# Resolver_to_digital_concerter_AD2S1210.net
KiCad netlist of a schematic drawn in EAGLE
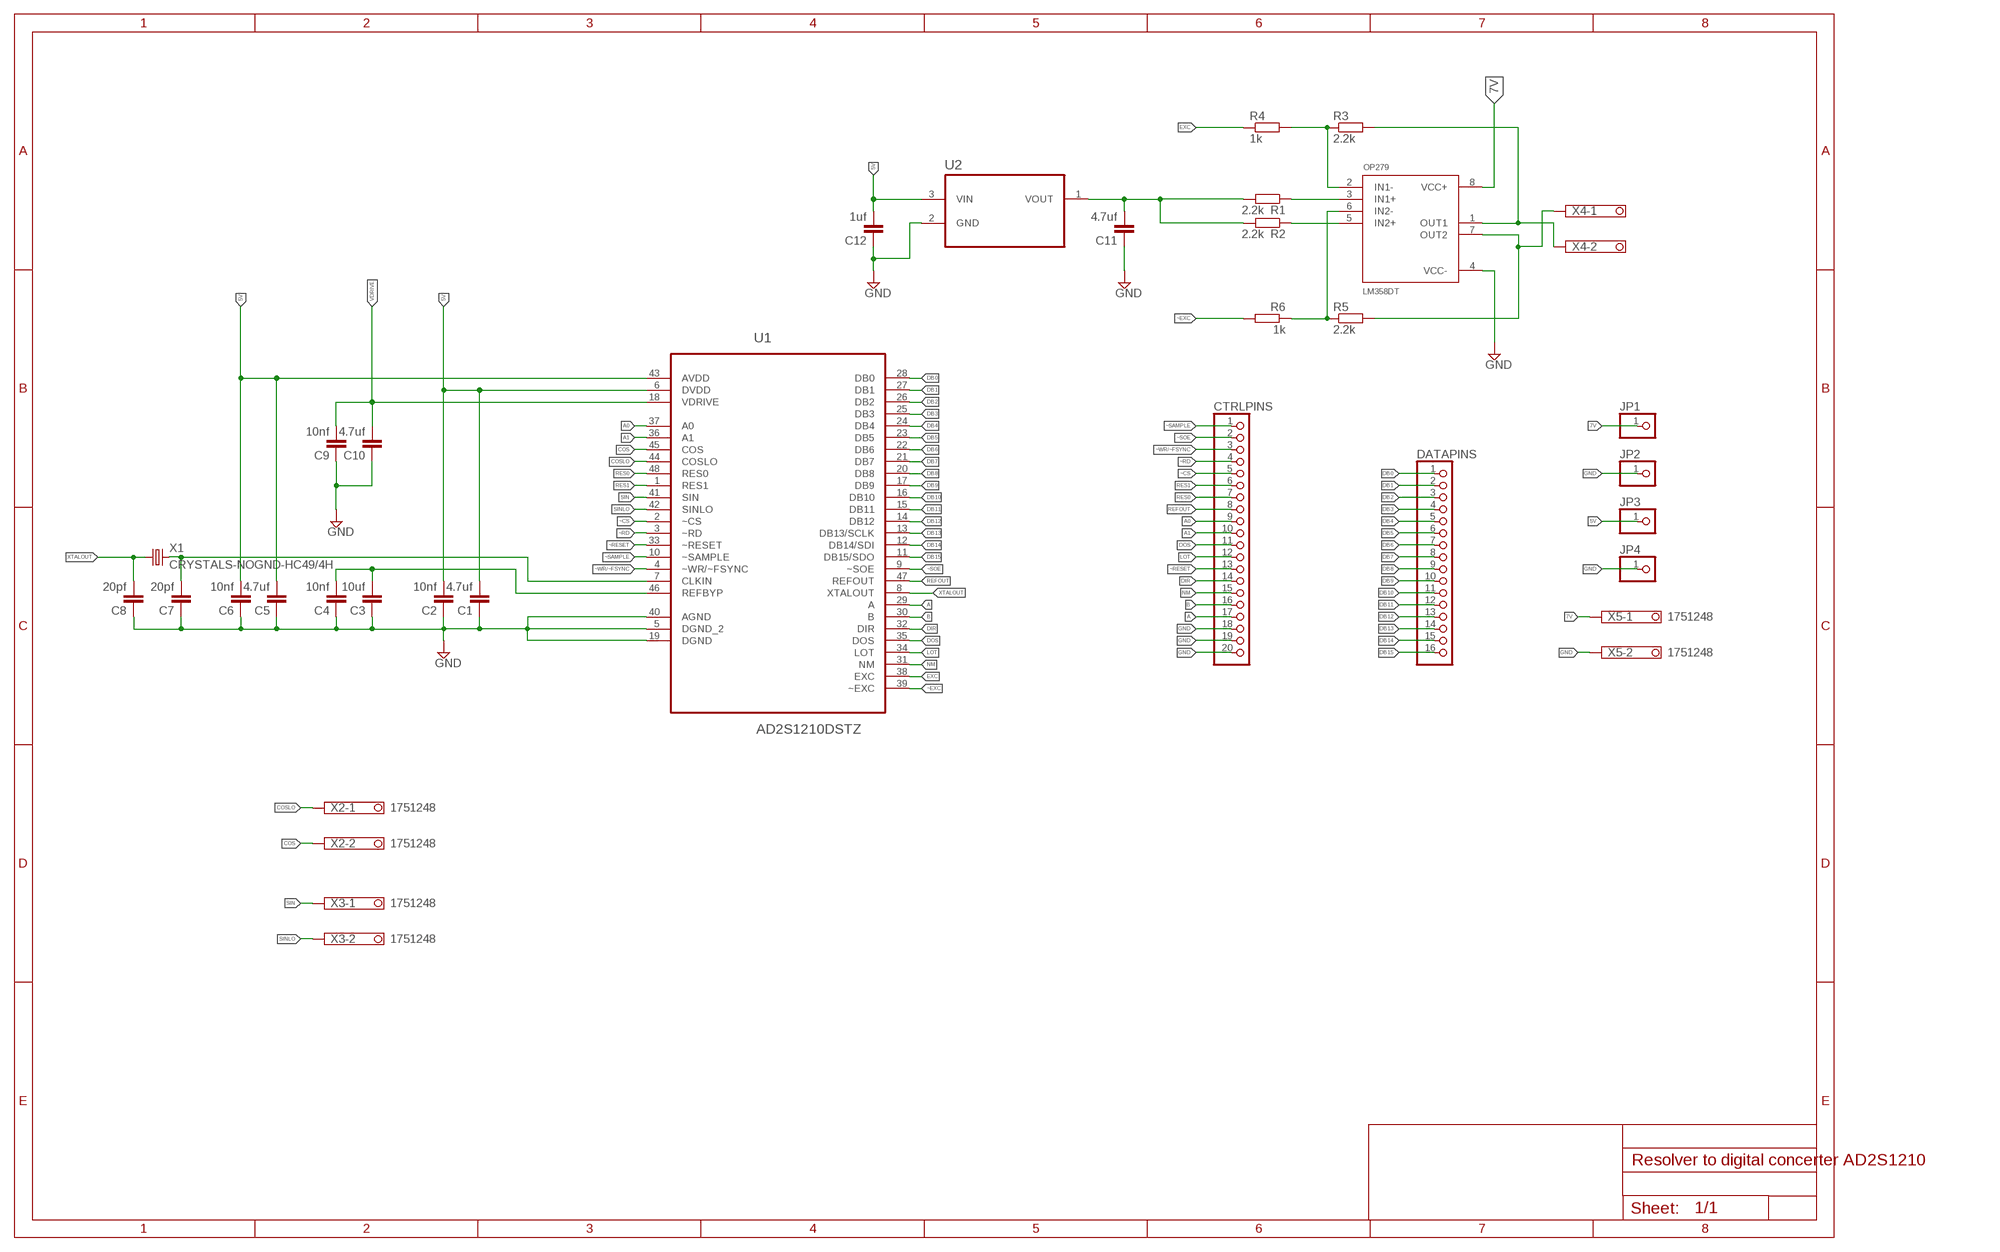
[diagram p0: schematic, sheet 1]

(export (version "E")
  (design (tool "Eeschema 10.0.6"))
  (components
    (comp (ref "C1")
      (value "4.7uf")
      (footprint "eagle-import:C0805")
      (libsource (lib "eagle-import") (part "C-EUC0805"))
    )
    (comp (ref "C2")
      (value "10nf")
      (footprint "eagle-import:C0805")
      (libsource (lib "eagle-import") (part "C-EUC0805"))
    )
    (comp (ref "C3")
      (value "10uf")
      (footprint "eagle-import:C0805")
      (libsource (lib "eagle-import") (part "C-EUC0805"))
    )
    (comp (ref "C4")
      (value "10nf")
      (footprint "eagle-import:C0805")
      (libsource (lib "eagle-import") (part "C-EUC0805"))
    )
    (comp (ref "C5")
      (value "4.7uf")
      (footprint "eagle-import:C0805")
      (libsource (lib "eagle-import") (part "C-EUC0805"))
    )
    (comp (ref "C6")
      (value "10nf")
      (footprint "eagle-import:C0805")
      (libsource (lib "eagle-import") (part "C-EUC0805"))
    )
    (comp (ref "C7")
      (value "20pf")
      (footprint "eagle-import:C0805")
      (libsource (lib "eagle-import") (part "C-EUC0805"))
    )
    (comp (ref "C8")
      (value "20pf")
      (footprint "eagle-import:C0805")
      (libsource (lib "eagle-import") (part "C-EUC0805"))
    )
    (comp (ref "C9")
      (value "10nf")
      (footprint "eagle-import:C0805")
      (libsource (lib "eagle-import") (part "C-EUC0805"))
    )
    (comp (ref "C10")
      (value "4.7uf")
      (footprint "eagle-import:C0805")
      (libsource (lib "eagle-import") (part "C-EUC0805"))
    )
    (comp (ref "C11")
      (value "4.7uf")
      (footprint "eagle-import:C0805")
      (libsource (lib "eagle-import") (part "C-EUC0805"))
    )
    (comp (ref "C12")
      (value "1uf")
      (footprint "eagle-import:C0805")
      (libsource (lib "eagle-import") (part "C-EUC0805"))
    )
    (comp (ref "CTRLPINS")
      (value "PINHD-1X20")
      (footprint "eagle-import:1X20")
      (libsource (lib "eagle-import") (part "PINHD-1X20"))
    )
    (comp (ref "DATAPINS")
      (value "PINHD-1X16")
      (footprint "eagle-import:1X16")
      (libsource (lib "eagle-import") (part "PINHD-1X16"))
    )
    (comp (ref "JP1")
      (value "PINHD-1X1")
      (footprint "eagle-import:1X01")
      (libsource (lib "eagle-import") (part "PINHD-1X1"))
    )
    (comp (ref "JP2")
      (value "PINHD-1X1")
      (footprint "eagle-import:1X01")
      (libsource (lib "eagle-import") (part "PINHD-1X1"))
    )
    (comp (ref "JP3")
      (value "PINHD-1X1")
      (footprint "eagle-import:1X01")
      (libsource (lib "eagle-import") (part "PINHD-1X1"))
    )
    (comp (ref "JP4")
      (value "PINHD-1X1")
      (footprint "eagle-import:1X01")
      (libsource (lib "eagle-import") (part "PINHD-1X1"))
    )
    (comp (ref "OP279")
      (value "LM358DT")
      (footprint "eagle-import:SOIC127P600X175-8N")
      (fields (field (name "MF") "STMicroelectronics"))
      (libsource (lib "eagle-import") (part "LM358DT"))
    )
    (comp (ref "R1")
      (value "2.2k")
      (footprint "eagle-import:R0805")
      (libsource (lib "eagle-import") (part "R-EU_R0805"))
    )
    (comp (ref "R2")
      (value "2.2k")
      (footprint "eagle-import:R0805")
      (libsource (lib "eagle-import") (part "R-EU_R0805"))
    )
    (comp (ref "R3")
      (value "2.2k")
      (footprint "eagle-import:R0805")
      (libsource (lib "eagle-import") (part "R-EU_R0805"))
    )
    (comp (ref "R4")
      (value "1k")
      (footprint "eagle-import:R0805")
      (libsource (lib "eagle-import") (part "R-EU_R0805"))
    )
    (comp (ref "R5")
      (value "2.2k")
      (footprint "eagle-import:R0805")
      (libsource (lib "eagle-import") (part "R-EU_R0805"))
    )
    (comp (ref "R6")
      (value "1k")
      (footprint "eagle-import:R0805")
      (libsource (lib "eagle-import") (part "R-EU_R0805"))
    )
    (comp (ref "U1")
      (value "AD2S1210DSTZ")
      (footprint "eagle-import:QFP50P900X900X160-48N")
      (fields (field (name "MF") "Analog Devices"))
      (libsource (lib "eagle-import") (part "AD2S1210DSTZ"))
    )
    (comp (ref "U2")
      (value "AD1582BRTZ-REEL7")
      (footprint "eagle-import:SOT95P237X112-3N")
      (fields (field (name "MF") "Analog Devices"))
      (libsource (lib "eagle-import") (part "AD1582BRTZ-REEL7"))
    )
    (comp (ref "X1")
      (value "CRYSTALS-NOGND-HC49/4H")
      (footprint "eagle-import:HC49")
      (libsource (lib "eagle-import") (part "CRYSTALS-NOGND-HC49/4H"))
    )
    (comp (ref "X2")
      (value "1751248")
      (footprint "eagle-import:1751248")
      (libsource (lib "eagle-import") (part "1751248"))
    )
    (comp (ref "X3")
      (value "1751248")
      (footprint "eagle-import:1751248")
      (libsource (lib "eagle-import") (part "1751248"))
    )
    (comp (ref "X4")
      (value "1751248")
      (footprint "eagle-import:1751248")
      (libsource (lib "eagle-import") (part "1751248"))
    )
    (comp (ref "X5")
      (value "1751248")
      (footprint "eagle-import:1751248")
      (libsource (lib "eagle-import") (part "1751248"))
    )
  )
  (nets
    (net (code "1") (name "/~{CS}") (class "Default")
      (node (ref "CTRLPINS") (pin "5") (pinfunction "5_5") (pintype "passive"))
      (node (ref "U1") (pin "2") (pinfunction "~{CS}_2") (pintype "input"))
    )
    (net (code "2") (name "/~{EXC}") (class "Default")
      (node (ref "R6") (pin "2") (pinfunction "2_2") (pintype "passive"))
      (node (ref "U1") (pin "39") (pinfunction "~{EXC}_39") (pintype "output"))
    )
    (net (code "3") (name "/~{RD}") (class "Default")
      (node (ref "CTRLPINS") (pin "4") (pinfunction "4_4") (pintype "passive"))
      (node (ref "U1") (pin "3") (pinfunction "~{RD}_3") (pintype "input"))
    )
    (net (code "4") (name "/~{RESET}") (class "Default")
      (node (ref "CTRLPINS") (pin "13") (pinfunction "13_13") (pintype "passive"))
      (node (ref "U1") (pin "33") (pinfunction "~{RESET}_33") (pintype "input"))
    )
    (net (code "5") (name "/~{SAMPLE}") (class "Default")
      (node (ref "CTRLPINS") (pin "1") (pinfunction "1_1") (pintype "passive"))
      (node (ref "U1") (pin "10") (pinfunction "~{SAMPLE}_10") (pintype "input"))
    )
    (net (code "6") (name "/~{SOE}") (class "Default")
      (node (ref "CTRLPINS") (pin "2") (pinfunction "2_2") (pintype "passive"))
      (node (ref "U1") (pin "9") (pinfunction "~{SOE}_9") (pintype "input"))
    )
    (net (code "7") (name "/~{WR{slash}}FSYNC") (class "Default")
      (node (ref "CTRLPINS") (pin "3") (pinfunction "3_3") (pintype "passive"))
      (node (ref "U1") (pin "4") (pinfunction "~{WR/}FSYNC_4") (pintype "input"))
    )
    (net (code "8") (name "5V") (class "Default")
      (node (ref "C1") (pin "2") (pinfunction "2_2") (pintype "passive"))
      (node (ref "C12") (pin "2") (pinfunction "2_2") (pintype "passive"))
      (node (ref "C2") (pin "2") (pinfunction "2_2") (pintype "passive"))
      (node (ref "C5") (pin "2") (pinfunction "2_2") (pintype "passive"))
      (node (ref "C6") (pin "2") (pinfunction "2_2") (pintype "passive"))
      (node (ref "JP3") (pin "1") (pinfunction "1_1") (pintype "passive"))
      (node (ref "U1") (pin "43") (pinfunction "AVDD_43") (pintype "power_in"))
      (node (ref "U1") (pin "6") (pinfunction "DVDD_6") (pintype "power_in"))
      (node (ref "U2") (pin "3") (pinfunction "VIN_3") (pintype "input"))
    )
    (net (code "9") (name "7V") (class "Default")
      (node (ref "JP1") (pin "1") (pinfunction "1_1") (pintype "passive"))
      (node (ref "OP279") (pin "8") (pinfunction "VCC+_8") (pintype "power_in"))
      (node (ref "X5") (pin "1") (pinfunction "K_1") (pintype "passive"))
    )
    (net (code "10") (name "A") (class "Default")
      (node (ref "CTRLPINS") (pin "17") (pinfunction "17_17") (pintype "passive"))
      (node (ref "U1") (pin "29") (pinfunction "A_29") (pintype "output"))
    )
    (net (code "11") (name "A0") (class "Default")
      (node (ref "CTRLPINS") (pin "9") (pinfunction "9_9") (pintype "passive"))
      (node (ref "U1") (pin "37") (pinfunction "A0_37") (pintype "input"))
    )
    (net (code "12") (name "A1") (class "Default")
      (node (ref "CTRLPINS") (pin "10") (pinfunction "10_10") (pintype "passive"))
      (node (ref "U1") (pin "36") (pinfunction "A1_36") (pintype "input"))
    )
    (net (code "13") (name "B") (class "Default")
      (node (ref "CTRLPINS") (pin "16") (pinfunction "16_16") (pintype "passive"))
      (node (ref "U1") (pin "30") (pinfunction "B_30") (pintype "output"))
    )
    (net (code "14") (name "COS") (class "Default")
      (node (ref "U1") (pin "45") (pinfunction "COS_45") (pintype "input"))
      (node (ref "X2") (pin "2") (pinfunction "K_2") (pintype "passive"))
    )
    (net (code "15") (name "COSLO") (class "Default")
      (node (ref "U1") (pin "44") (pinfunction "COSLO_44") (pintype "input"))
      (node (ref "X2") (pin "1") (pinfunction "K_1") (pintype "passive"))
    )
    (net (code "16") (name "DB0") (class "Default")
      (node (ref "DATAPINS") (pin "1") (pinfunction "1_1") (pintype "passive"))
      (node (ref "U1") (pin "28") (pinfunction "DB0_28") (pintype "output"))
    )
    (net (code "17") (name "DB1") (class "Default")
      (node (ref "DATAPINS") (pin "2") (pinfunction "2_2") (pintype "passive"))
      (node (ref "U1") (pin "27") (pinfunction "DB1_27") (pintype "output"))
    )
    (net (code "18") (name "DB2") (class "Default")
      (node (ref "DATAPINS") (pin "3") (pinfunction "3_3") (pintype "passive"))
      (node (ref "U1") (pin "26") (pinfunction "DB2_26") (pintype "output"))
    )
    (net (code "19") (name "DB3") (class "Default")
      (node (ref "DATAPINS") (pin "4") (pinfunction "4_4") (pintype "passive"))
      (node (ref "U1") (pin "25") (pinfunction "DB3_25") (pintype "output"))
    )
    (net (code "20") (name "DB4") (class "Default")
      (node (ref "DATAPINS") (pin "5") (pinfunction "5_5") (pintype "passive"))
      (node (ref "U1") (pin "24") (pinfunction "DB4_24") (pintype "output"))
    )
    (net (code "21") (name "DB5") (class "Default")
      (node (ref "DATAPINS") (pin "6") (pinfunction "6_6") (pintype "passive"))
      (node (ref "U1") (pin "23") (pinfunction "DB5_23") (pintype "output"))
    )
    (net (code "22") (name "DB6") (class "Default")
      (node (ref "DATAPINS") (pin "7") (pinfunction "7_7") (pintype "passive"))
      (node (ref "U1") (pin "22") (pinfunction "DB6_22") (pintype "output"))
    )
    (net (code "23") (name "DB7") (class "Default")
      (node (ref "DATAPINS") (pin "8") (pinfunction "8_8") (pintype "passive"))
      (node (ref "U1") (pin "21") (pinfunction "DB7_21") (pintype "output"))
    )
    (net (code "24") (name "DB8") (class "Default")
      (node (ref "DATAPINS") (pin "9") (pinfunction "9_9") (pintype "passive"))
      (node (ref "U1") (pin "20") (pinfunction "DB8_20") (pintype "output"))
    )
    (net (code "25") (name "DB9") (class "Default")
      (node (ref "DATAPINS") (pin "10") (pinfunction "10_10") (pintype "passive"))
      (node (ref "U1") (pin "17") (pinfunction "DB9_17") (pintype "output"))
    )
    (net (code "26") (name "DB10") (class "Default")
      (node (ref "DATAPINS") (pin "11") (pinfunction "11_11") (pintype "passive"))
      (node (ref "U1") (pin "16") (pinfunction "DB10_16") (pintype "output"))
    )
    (net (code "27") (name "DB11") (class "Default")
      (node (ref "DATAPINS") (pin "12") (pinfunction "12_12") (pintype "passive"))
      (node (ref "U1") (pin "15") (pinfunction "DB11_15") (pintype "output"))
    )
    (net (code "28") (name "DB12") (class "Default")
      (node (ref "DATAPINS") (pin "13") (pinfunction "13_13") (pintype "passive"))
      (node (ref "U1") (pin "14") (pinfunction "DB12_14") (pintype "output"))
    )
    (net (code "29") (name "DB13") (class "Default")
      (node (ref "DATAPINS") (pin "14") (pinfunction "14_14") (pintype "passive"))
      (node (ref "U1") (pin "13") (pinfunction "DB13/SCLK_13") (pintype "bidirectional"))
    )
    (net (code "30") (name "DB14") (class "Default")
      (node (ref "DATAPINS") (pin "15") (pinfunction "15_15") (pintype "passive"))
      (node (ref "U1") (pin "12") (pinfunction "DB14/SDI_12") (pintype "bidirectional"))
    )
    (net (code "31") (name "DB15") (class "Default")
      (node (ref "DATAPINS") (pin "16") (pinfunction "16_16") (pintype "passive"))
      (node (ref "U1") (pin "11") (pinfunction "DB15/SDO_11") (pintype "output"))
    )
    (net (code "32") (name "DIR") (class "Default")
      (node (ref "CTRLPINS") (pin "14") (pinfunction "14_14") (pintype "passive"))
      (node (ref "U1") (pin "32") (pinfunction "DIR_32") (pintype "output"))
    )
    (net (code "33") (name "DOS") (class "Default")
      (node (ref "CTRLPINS") (pin "11") (pinfunction "11_11") (pintype "passive"))
      (node (ref "U1") (pin "35") (pinfunction "DOS_35") (pintype "output"))
    )
    (net (code "34") (name "EXC") (class "Default")
      (node (ref "R4") (pin "1") (pinfunction "1_1") (pintype "passive"))
      (node (ref "U1") (pin "38") (pinfunction "EXC_38") (pintype "output"))
    )
    (net (code "35") (name "GND") (class "Default")
      (node (ref "C1") (pin "1") (pinfunction "1_1") (pintype "passive"))
      (node (ref "C10") (pin "1") (pinfunction "1_1") (pintype "passive"))
      (node (ref "C11") (pin "1") (pinfunction "1_1") (pintype "passive"))
      (node (ref "C12") (pin "1") (pinfunction "1_1") (pintype "passive"))
      (node (ref "C2") (pin "1") (pinfunction "1_1") (pintype "passive"))
      (node (ref "C3") (pin "1") (pinfunction "1_1") (pintype "passive"))
      (node (ref "C4") (pin "1") (pinfunction "1_1") (pintype "passive"))
      (node (ref "C5") (pin "1") (pinfunction "1_1") (pintype "passive"))
      (node (ref "C6") (pin "1") (pinfunction "1_1") (pintype "passive"))
      (node (ref "C7") (pin "1") (pinfunction "1_1") (pintype "passive"))
      (node (ref "C8") (pin "1") (pinfunction "1_1") (pintype "passive"))
      (node (ref "C9") (pin "1") (pinfunction "1_1") (pintype "passive"))
      (node (ref "CTRLPINS") (pin "18") (pinfunction "18_18") (pintype "passive"))
      (node (ref "CTRLPINS") (pin "19") (pinfunction "19_19") (pintype "passive"))
      (node (ref "CTRLPINS") (pin "20") (pinfunction "20_20") (pintype "passive"))
      (node (ref "JP2") (pin "1") (pinfunction "1_1") (pintype "passive"))
      (node (ref "JP4") (pin "1") (pinfunction "1_1") (pintype "passive"))
      (node (ref "OP279") (pin "4") (pinfunction "VCC-_4") (pintype "power_in"))
      (node (ref "U1") (pin "19") (pinfunction "DGND_19") (pintype "passive"))
      (node (ref "U1") (pin "40") (pinfunction "AGND_40") (pintype "passive"))
      (node (ref "U1") (pin "5") (pinfunction "DGND_2_5") (pintype "passive"))
      (node (ref "U2") (pin "2") (pinfunction "GND_2") (pintype "passive"))
      (node (ref "X5") (pin "2") (pinfunction "K_2") (pintype "passive"))
    )
    (net (code "36") (name "LOT") (class "Default")
      (node (ref "CTRLPINS") (pin "12") (pinfunction "12_12") (pintype "passive"))
      (node (ref "U1") (pin "34") (pinfunction "LOT_34") (pintype "output"))
    )
    (net (code "37") (name "NM") (class "Default")
      (node (ref "CTRLPINS") (pin "15") (pinfunction "15_15") (pintype "passive"))
      (node (ref "U1") (pin "31") (pinfunction "NM_31") (pintype "output"))
    )
    (net (code "38") (name "Net-(OP279-IN1+)") (class "Default")
      (node (ref "OP279") (pin "3") (pinfunction "IN1+_3") (pintype "input"))
      (node (ref "R1") (pin "1") (pinfunction "1_1") (pintype "passive"))
    )
    (net (code "39") (name "Net-(OP279-IN1-)") (class "Default")
      (node (ref "OP279") (pin "2") (pinfunction "IN1-_2") (pintype "input"))
      (node (ref "R3") (pin "1") (pinfunction "1_1") (pintype "passive"))
      (node (ref "R4") (pin "2") (pinfunction "2_2") (pintype "passive"))
    )
    (net (code "40") (name "Net-(OP279-IN2+)") (class "Default")
      (node (ref "OP279") (pin "5") (pinfunction "IN2+_5") (pintype "input"))
      (node (ref "R2") (pin "1") (pinfunction "1_1") (pintype "passive"))
    )
    (net (code "41") (name "Net-(OP279-IN2-)") (class "Default")
      (node (ref "OP279") (pin "6") (pinfunction "IN2-_6") (pintype "input"))
      (node (ref "R5") (pin "1") (pinfunction "1_1") (pintype "passive"))
      (node (ref "R6") (pin "1") (pinfunction "1_1") (pintype "passive"))
    )
    (net (code "42") (name "Net-(OP279-OUT1)") (class "Default")
      (node (ref "OP279") (pin "1") (pinfunction "OUT1_1") (pintype "output"))
      (node (ref "R3") (pin "2") (pinfunction "2_2") (pintype "passive"))
      (node (ref "X4") (pin "2") (pinfunction "K_2") (pintype "passive"))
    )
    (net (code "43") (name "Net-(OP279-OUT2)") (class "Default")
      (node (ref "OP279") (pin "7") (pinfunction "OUT2_7") (pintype "output"))
      (node (ref "R5") (pin "2") (pinfunction "2_2") (pintype "passive"))
      (node (ref "X4") (pin "1") (pinfunction "K_1") (pintype "passive"))
    )
    (net (code "44") (name "Net-(U1-CLKIN)") (class "Default")
      (node (ref "C7") (pin "2") (pinfunction "2_2") (pintype "passive"))
      (node (ref "U1") (pin "7") (pinfunction "CLKIN_7") (pintype "input"))
      (node (ref "X1") (pin "2") (pinfunction "2_2") (pintype "passive"))
    )
    (net (code "45") (name "Net-(U1-REFBYP)") (class "Default")
      (node (ref "C3") (pin "2") (pinfunction "2_2") (pintype "passive"))
      (node (ref "C4") (pin "2") (pinfunction "2_2") (pintype "passive"))
      (node (ref "U1") (pin "46") (pinfunction "REFBYP_46") (pintype "passive"))
    )
    (net (code "46") (name "Net-(U2-VOUT)") (class "Default")
      (node (ref "C11") (pin "2") (pinfunction "2_2") (pintype "passive"))
      (node (ref "R1") (pin "2") (pinfunction "2_2") (pintype "passive"))
      (node (ref "R2") (pin "2") (pinfunction "2_2") (pintype "passive"))
      (node (ref "U2") (pin "1") (pinfunction "VOUT_1") (pintype "output"))
    )
    (net (code "47") (name "REFOUT") (class "Default")
      (node (ref "CTRLPINS") (pin "8") (pinfunction "8_8") (pintype "passive"))
      (node (ref "U1") (pin "47") (pinfunction "REFOUT_47") (pintype "output"))
    )
    (net (code "48") (name "RES0") (class "Default")
      (node (ref "CTRLPINS") (pin "7") (pinfunction "7_7") (pintype "passive"))
      (node (ref "U1") (pin "48") (pinfunction "RES0_48") (pintype "input"))
    )
    (net (code "49") (name "RES1") (class "Default")
      (node (ref "CTRLPINS") (pin "6") (pinfunction "6_6") (pintype "passive"))
      (node (ref "U1") (pin "1") (pinfunction "RES1_1") (pintype "input"))
    )
    (net (code "50") (name "SIN") (class "Default")
      (node (ref "U1") (pin "41") (pinfunction "SIN_41") (pintype "input"))
      (node (ref "X3") (pin "1") (pinfunction "K_1") (pintype "passive"))
    )
    (net (code "51") (name "SINLO") (class "Default")
      (node (ref "U1") (pin "42") (pinfunction "SINLO_42") (pintype "input"))
      (node (ref "X3") (pin "2") (pinfunction "K_2") (pintype "passive"))
    )
    (net (code "52") (name "VDRIVE") (class "Default")
      (node (ref "C10") (pin "2") (pinfunction "2_2") (pintype "passive"))
      (node (ref "C9") (pin "2") (pinfunction "2_2") (pintype "passive"))
      (node (ref "U1") (pin "18") (pinfunction "VDRIVE_18") (pintype "power_in"))
    )
    (net (code "53") (name "XTALOUT") (class "Default")
      (node (ref "C8") (pin "2") (pinfunction "2_2") (pintype "passive"))
      (node (ref "U1") (pin "8") (pinfunction "XTALOUT_8") (pintype "output"))
      (node (ref "X1") (pin "1") (pinfunction "1_1") (pintype "passive"))
    )
  )
)
